# schematic.net
KiCad netlist of a schematic drawn in EAGLE
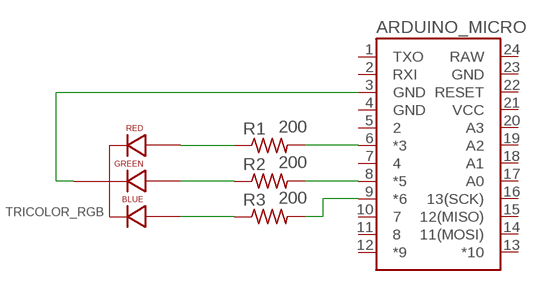
[diagram p0: schematic, sheet 1]

(export (version "E")
  (design (tool "Eeschema 10.0.6"))
  (components
    (comp (ref "ARDUINO_MICRO")
      (value "ARDUINO_PRO_MICRO")
      (footprint "eagle-import:ARDUINO_PRO_MICRO")
      (libsource (lib "eagle-import") (part "ARDUINO_PRO_MICRO"))
    )
    (comp (ref "R1")
      (value "200")
      (footprint "eagle-import:0204V")
      (libsource (lib "eagle-import") (part "R-US_0204/2V"))
    )
    (comp (ref "R2")
      (value "200")
      (footprint "eagle-import:0204V")
      (libsource (lib "eagle-import") (part "R-US_0204/2V"))
    )
    (comp (ref "R3")
      (value "200")
      (footprint "eagle-import:0204V")
      (libsource (lib "eagle-import") (part "R-US_0204/2V"))
    )
    (comp (ref "TRICOLOR_RGB")
      (value "LED-RGB-CC-THRUCLEAR")
      (footprint "eagle-import:LED-RGB-THRU")
      (libsource (lib "eagle-import") (part "LED-RGB-CC-THRUCLEAR"))
    )
  )
  (nets
    (net (code "1") (name "Net-(ARDUINO_MICRO-*3)") (class "Default")
      (node (ref "ARDUINO_MICRO") (pin "6") (pinfunction "*3_6") (pintype "bidirectional"))
      (node (ref "R1") (pin "2") (pinfunction "2_2") (pintype "passive"))
    )
    (net (code "2") (name "Net-(ARDUINO_MICRO-*5)") (class "Default")
      (node (ref "ARDUINO_MICRO") (pin "8") (pinfunction "*5_8") (pintype "bidirectional"))
      (node (ref "R2") (pin "2") (pinfunction "2_2") (pintype "passive"))
    )
    (net (code "3") (name "Net-(ARDUINO_MICRO-*6)") (class "Default")
      (node (ref "ARDUINO_MICRO") (pin "9") (pinfunction "*6_9") (pintype "bidirectional"))
      (node (ref "R3") (pin "2") (pinfunction "2_2") (pintype "passive"))
    )
    (net (code "4") (name "Net-(TRICOLOR_RGB-BLUE_CATHODE)") (class "Default")
      (node (ref "R3") (pin "1") (pinfunction "1_1") (pintype "passive"))
      (node (ref "TRICOLOR_RGB") (pin "4") (pinfunction "BLUE_CATHODE_4") (pintype "bidirectional"))
    )
    (net (code "5") (name "Net-(TRICOLOR_RGB-CATHODE)") (class "Default")
      (node (ref "ARDUINO_MICRO") (pin "3") (pinfunction "GND_3") (pintype "bidirectional"))
      (node (ref "TRICOLOR_RGB") (pin "2") (pinfunction "CATHODE_2") (pintype "bidirectional"))
    )
    (net (code "6") (name "Net-(TRICOLOR_RGB-GREEN_CATHODE)") (class "Default")
      (node (ref "R2") (pin "1") (pinfunction "1_1") (pintype "passive"))
      (node (ref "TRICOLOR_RGB") (pin "3") (pinfunction "GREEN_CATHODE_3") (pintype "bidirectional"))
    )
    (net (code "7") (name "Net-(TRICOLOR_RGB-RED_CATHODE)") (class "Default")
      (node (ref "R1") (pin "1") (pinfunction "1_1") (pintype "passive"))
      (node (ref "TRICOLOR_RGB") (pin "1") (pinfunction "RED_CATHODE_1") (pintype "bidirectional"))
    )
    (net (code "8") (name "unconnected-(ARDUINO_MICRO-*9-Pad12)") (class "Default")
      (node (ref "ARDUINO_MICRO") (pin "12") (pinfunction "*9_12") (pintype "bidirectional"))
    )
    (net (code "9") (name "unconnected-(ARDUINO_MICRO-*10-Pad13)") (class "Default")
      (node (ref "ARDUINO_MICRO") (pin "13") (pinfunction "*10_13") (pintype "bidirectional"))
    )
    (net (code "10") (name "unconnected-(ARDUINO_MICRO-2-Pad5)") (class "Default")
      (node (ref "ARDUINO_MICRO") (pin "5") (pinfunction "2_5") (pintype "bidirectional"))
    )
    (net (code "11") (name "unconnected-(ARDUINO_MICRO-4-Pad7)") (class "Default")
      (node (ref "ARDUINO_MICRO") (pin "7") (pinfunction "4_7") (pintype "bidirectional"))
    )
    (net (code "12") (name "unconnected-(ARDUINO_MICRO-7-Pad10)") (class "Default")
      (node (ref "ARDUINO_MICRO") (pin "10") (pinfunction "7_10") (pintype "bidirectional"))
    )
    (net (code "13") (name "unconnected-(ARDUINO_MICRO-8-Pad11)") (class "Default")
      (node (ref "ARDUINO_MICRO") (pin "11") (pinfunction "8_11") (pintype "bidirectional"))
    )
    (net (code "14") (name "unconnected-(ARDUINO_MICRO-11(MOSI)-Pad14)") (class "Default")
      (node (ref "ARDUINO_MICRO") (pin "14") (pinfunction "11(MOSI)_14") (pintype "bidirectional"))
    )
    (net (code "15") (name "unconnected-(ARDUINO_MICRO-12(MISO)-Pad15)") (class "Default")
      (node (ref "ARDUINO_MICRO") (pin "15") (pinfunction "12(MISO)_15") (pintype "bidirectional"))
    )
    (net (code "16") (name "unconnected-(ARDUINO_MICRO-13(SCK)-Pad16)") (class "Default")
      (node (ref "ARDUINO_MICRO") (pin "16") (pinfunction "13(SCK)_16") (pintype "bidirectional"))
    )
    (net (code "17") (name "unconnected-(ARDUINO_MICRO-A0-Pad17)") (class "Default")
      (node (ref "ARDUINO_MICRO") (pin "17") (pinfunction "A0_17") (pintype "bidirectional"))
    )
    (net (code "18") (name "unconnected-(ARDUINO_MICRO-A1-Pad18)") (class "Default")
      (node (ref "ARDUINO_MICRO") (pin "18") (pinfunction "A1_18") (pintype "bidirectional"))
    )
    (net (code "19") (name "unconnected-(ARDUINO_MICRO-A2-Pad19)") (class "Default")
      (node (ref "ARDUINO_MICRO") (pin "19") (pinfunction "A2_19") (pintype "bidirectional"))
    )
    (net (code "20") (name "unconnected-(ARDUINO_MICRO-A3-Pad20)") (class "Default")
      (node (ref "ARDUINO_MICRO") (pin "20") (pinfunction "A3_20") (pintype "bidirectional"))
    )
    (net (code "21") (name "unconnected-(ARDUINO_MICRO-GND-Pad4)") (class "Default")
      (node (ref "ARDUINO_MICRO") (pin "4") (pinfunction "GND_4") (pintype "bidirectional"))
    )
    (net (code "22") (name "unconnected-(ARDUINO_MICRO-GND-Pad23)") (class "Default")
      (node (ref "ARDUINO_MICRO") (pin "23") (pinfunction "GND_23") (pintype "bidirectional"))
    )
    (net (code "23") (name "unconnected-(ARDUINO_MICRO-RAW-Pad24)") (class "Default")
      (node (ref "ARDUINO_MICRO") (pin "24") (pinfunction "RAW_24") (pintype "bidirectional"))
    )
    (net (code "24") (name "unconnected-(ARDUINO_MICRO-RESET-Pad22)") (class "Default")
      (node (ref "ARDUINO_MICRO") (pin "22") (pinfunction "RESET_22") (pintype "bidirectional"))
    )
    (net (code "25") (name "unconnected-(ARDUINO_MICRO-RXI-Pad2)") (class "Default")
      (node (ref "ARDUINO_MICRO") (pin "2") (pinfunction "RXI_2") (pintype "bidirectional"))
    )
    (net (code "26") (name "unconnected-(ARDUINO_MICRO-TXO-Pad1)") (class "Default")
      (node (ref "ARDUINO_MICRO") (pin "1") (pinfunction "TXO_1") (pintype "bidirectional"))
    )
    (net (code "27") (name "unconnected-(ARDUINO_MICRO-VCC-Pad21)") (class "Default")
      (node (ref "ARDUINO_MICRO") (pin "21") (pinfunction "VCC_21") (pintype "bidirectional"))
    )
  )
)
